# PCB.net
KiCad netlist of a schematic drawn in EasyEDA Pro
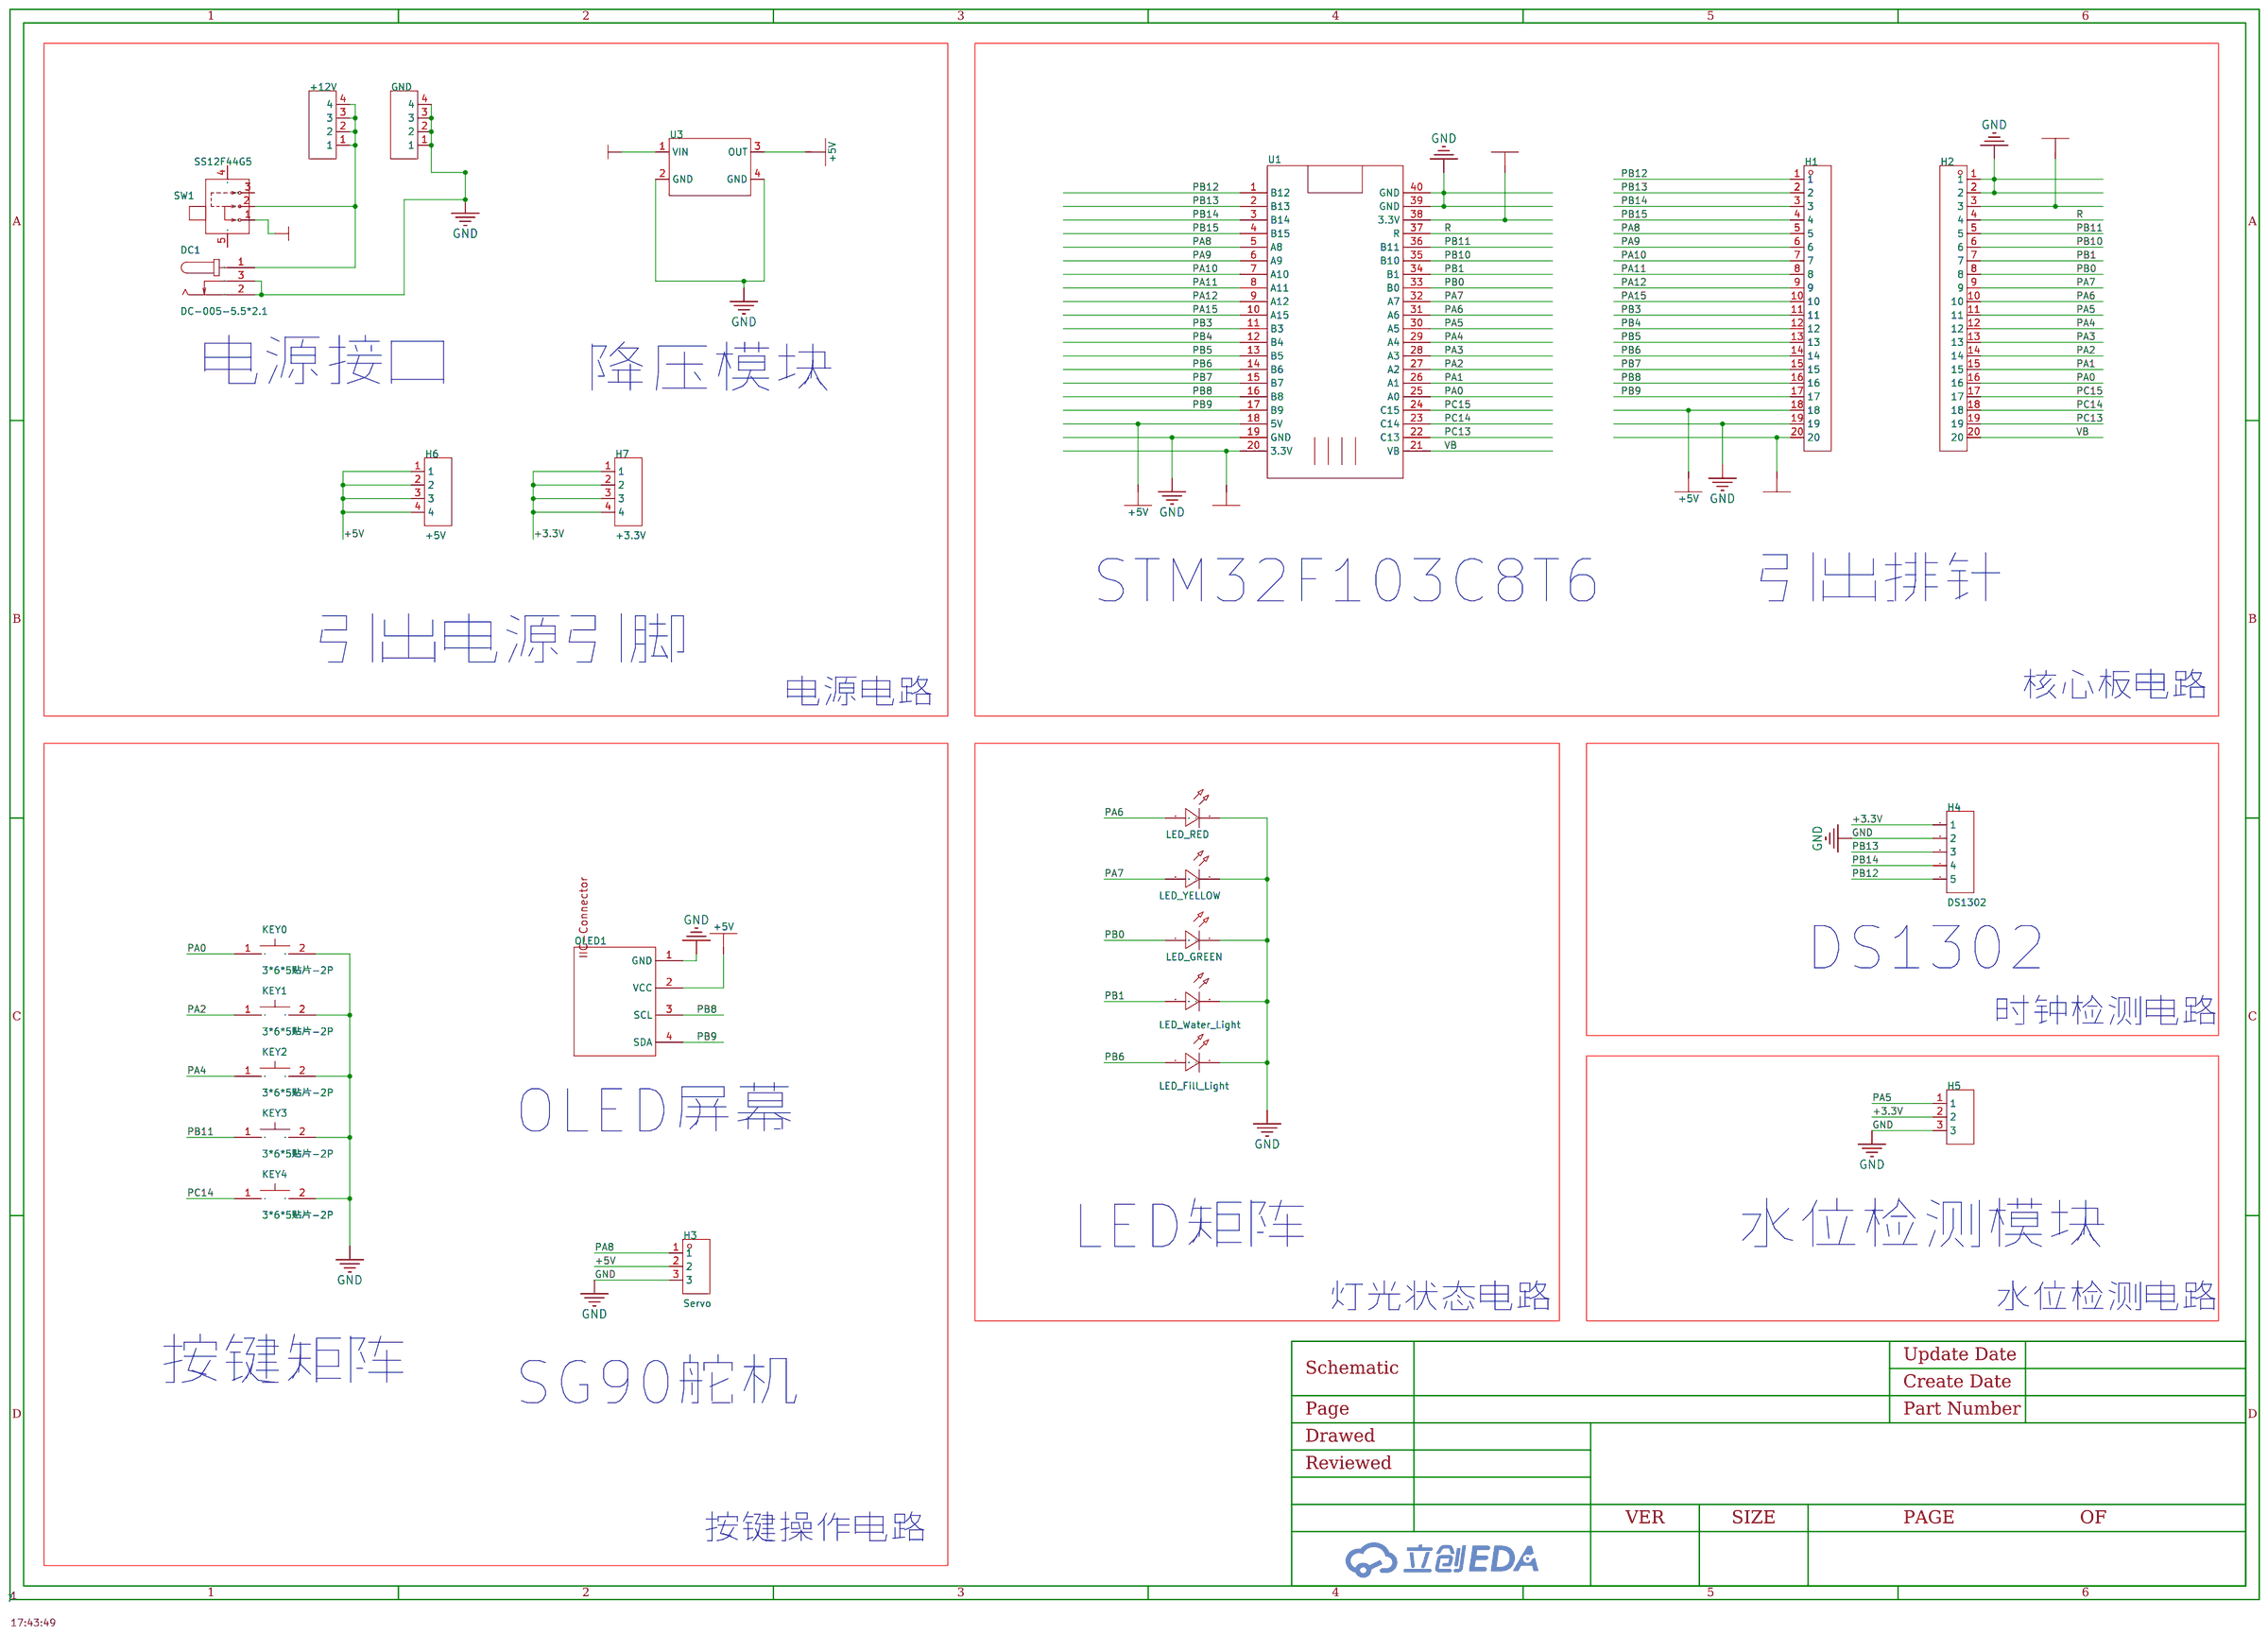
[diagram p0: schematic sheet]

(export (version "E")
  (design (tool "Eeschema 10.0.6"))
  (components
    (comp (ref "+12V")
      (value "~")
      (footprint "easyedapro:HDR-TH_4P-P2.54-V-M")
      (libsource (lib "easyedapro") (part "PZ254V-11-04P"))
    )
    (comp (ref "DC1")
      (value "DC-005-5.5*2.1")
      (footprint "easyedapro:DC-IN-TH_DC-005-2")
      (libsource (lib "easyedapro") (part "DC-005-5.5*2.1"))
    )
    (comp (ref "GND")
      (value "~")
      (footprint "easyedapro:HDR-TH_4P-P2.54-V-M")
      (libsource (lib "easyedapro") (part "PZ254V-11-04P"))
    )
    (comp (ref "H1")
      (value "~")
      (footprint "easyedapro:HDR-TH_20P-P2.54-V-M-1")
      (libsource (lib "easyedapro") (part "HDR_2.54-1x20P"))
    )
    (comp (ref "H2")
      (value "~")
      (footprint "easyedapro:HDR-TH_20P-P2.54-V-M-1")
      (libsource (lib "easyedapro") (part "HDR_2.54-1x20P"))
    )
    (comp (ref "H3")
      (value "Servo")
      (footprint "easyedapro:HDR-TH_3P-P2.54-V-M")
      (libsource (lib "easyedapro") (part "HDR-M_2.54_1x3P"))
    )
    (comp (ref "H4")
      (value "DS1302")
      (footprint "easyedapro:HDR-TH_5P-P2.54-V-F")
      (libsource (lib "easyedapro") (part "Header-Female-2.54_1x5"))
    )
    (comp (ref "H5")
      (value "~")
      (footprint "easyedapro:HDR-TH_3P-P2.54-V-F")
      (libsource (lib "easyedapro") (part "PM254V-11-03-H85"))
    )
    (comp (ref "H6")
      (value "+5V")
      (footprint "easyedapro:HDR-TH_4P-P2.54-V-M")
      (libsource (lib "easyedapro") (part "PZ254V-11-04P"))
    )
    (comp (ref "H7")
      (value "+3.3V")
      (footprint "easyedapro:HDR-TH_4P-P2.54-V-M")
      (libsource (lib "easyedapro") (part "PZ254V-11-04P"))
    )
    (comp (ref "KEY0")
      (value "3*6*5贴片-2P")
      (footprint "easyedapro:SW-SMD_L6.0-W3.5-LS8.0")
      (libsource (lib "easyedapro") (part "3*6*5贴片-2P"))
    )
    (comp (ref "KEY1")
      (value "3*6*5贴片-2P")
      (footprint "easyedapro:SW-SMD_L6.0-W3.5-LS8.0")
      (libsource (lib "easyedapro") (part "3*6*5贴片-2P"))
    )
    (comp (ref "KEY2")
      (value "3*6*5贴片-2P")
      (footprint "easyedapro:SW-SMD_L6.0-W3.5-LS8.0")
      (libsource (lib "easyedapro") (part "3*6*5贴片-2P"))
    )
    (comp (ref "KEY3")
      (value "3*6*5贴片-2P")
      (footprint "easyedapro:SW-SMD_L6.0-W3.5-LS8.0")
      (libsource (lib "easyedapro") (part "3*6*5贴片-2P"))
    )
    (comp (ref "KEY4")
      (value "3*6*5贴片-2P")
      (footprint "easyedapro:SW-SMD_L6.0-W3.5-LS8.0")
      (libsource (lib "easyedapro") (part "3*6*5贴片-2P"))
    )
    (comp (ref "LED_Fill_Light")
      (value "~")
      (footprint "easyedapro:LED_TH-_5mm")
      (libsource (lib "easyedapro") (part "LED_TH-B"))
    )
    (comp (ref "LED_GREEN")
      (value "~")
      (footprint "easyedapro:LED_TH-_5mm")
      (libsource (lib "easyedapro") (part "LED_TH-G"))
    )
    (comp (ref "LED_RED")
      (value "~")
      (footprint "easyedapro:LED_TH-_5mm")
      (libsource (lib "easyedapro") (part "LED_TH-R"))
    )
    (comp (ref "LED_Water_Light")
      (value "~")
      (footprint "easyedapro:LED_TH-_5mm")
      (libsource (lib "easyedapro") (part "LED_TH-B"))
    )
    (comp (ref "LED_YELLOW")
      (value "~")
      (footprint "easyedapro:LED_TH-_5mm")
      (libsource (lib "easyedapro") (part "LED_TH-B"))
    )
    (comp (ref "OLED1")
      (value "~")
      (fields (field (name "Manufacturer Part") "0.96OLED_4P_MODULE_JX"))
      (libsource (lib "easyedapro") (part "0.96OLED_4P_MODULE_JX"))
    )
    (comp (ref "SW1")
      (value "SS12F44G5")
      (footprint "easyedapro:SW-TH_SHOU-HAN_SS12F44G4")
      (description "拨动开关 立式直脚插件 二档 柄高5mm")
      (fields (field (name "Manufacturer") "HanElectricity(瀚源)"))
      (libsource (lib "easyedapro") (part "SS12F44G5"))
    )
    (comp (ref "U1") (value "~") (libsource (lib "easyedapro") (part "STM32F103C8T6核心板")))
    (comp (ref "U3")
      (value "~")
      (footprint "easyedapro:MP1584模块")
      (libsource (lib "easyedapro") (part "MP1584模块"))
    )
  )
  (nets
    (net (code "1") (name "+3.3V") (class "Default")
      (node (ref "H1") (pin "20") (pinfunction "20_20") (pintype "input"))
      (node (ref "H2") (pin "3") (pinfunction "3_3") (pintype "input"))
      (node (ref "H4") (pin "1") (pinfunction "1_1") (pintype "input"))
      (node (ref "H5") (pin "2") (pinfunction "2_2") (pintype "unspecified"))
      (node (ref "H7") (pin "1") (pinfunction "1_1") (pintype "unspecified"))
      (node (ref "H7") (pin "2") (pinfunction "2_2") (pintype "unspecified"))
      (node (ref "H7") (pin "3") (pinfunction "3_3") (pintype "unspecified"))
      (node (ref "H7") (pin "4") (pinfunction "4_4") (pintype "unspecified"))
      (node (ref "U1") (pin "20") (pinfunction "3.3V_20") (pintype "unspecified"))
      (node (ref "U1") (pin "38") (pinfunction "3.3V_38") (pintype "unspecified"))
    )
    (net (code "2") (name "+5V") (class "Default")
      (node (ref "H1") (pin "18") (pinfunction "18_18") (pintype "input"))
      (node (ref "H3") (pin "2") (pinfunction "2_2") (pintype "input"))
      (node (ref "H6") (pin "1") (pinfunction "1_1") (pintype "unspecified"))
      (node (ref "H6") (pin "2") (pinfunction "2_2") (pintype "unspecified"))
      (node (ref "H6") (pin "3") (pinfunction "3_3") (pintype "unspecified"))
      (node (ref "H6") (pin "4") (pinfunction "4_4") (pintype "unspecified"))
      (node (ref "OLED1") (pin "2") (pinfunction "VCC_2") (pintype "input"))
      (node (ref "U1") (pin "18") (pinfunction "5V_18") (pintype "unspecified"))
      (node (ref "U3") (pin "3") (pinfunction "OUT_3") (pintype "unspecified"))
    )
    (net (code "3") (name "+12V") (class "Default")
      (node (ref "SW1") (pin "1") (pinfunction "1_1") (pintype "unspecified"))
      (node (ref "U3") (pin "1") (pinfunction "VIN_1") (pintype "unspecified"))
    )
    (net (code "4") (name "/PA0") (class "Default")
      (node (ref "H2") (pin "16") (pinfunction "16_16") (pintype "input"))
      (node (ref "KEY0") (pin "1") (pinfunction "1_1") (pintype "unspecified"))
      (node (ref "U1") (pin "25") (pinfunction "A0_25") (pintype "unspecified"))
    )
    (net (code "5") (name "/PA1") (class "Default")
      (node (ref "H2") (pin "15") (pinfunction "15_15") (pintype "input"))
      (node (ref "U1") (pin "26") (pinfunction "A1_26") (pintype "unspecified"))
    )
    (net (code "6") (name "/PA2") (class "Default")
      (node (ref "H2") (pin "14") (pinfunction "14_14") (pintype "input"))
      (node (ref "KEY1") (pin "1") (pinfunction "1_1") (pintype "unspecified"))
      (node (ref "U1") (pin "27") (pinfunction "A2_27") (pintype "unspecified"))
    )
    (net (code "7") (name "/PA3") (class "Default")
      (node (ref "H2") (pin "13") (pinfunction "13_13") (pintype "input"))
      (node (ref "U1") (pin "28") (pinfunction "A3_28") (pintype "unspecified"))
    )
    (net (code "8") (name "/PA4") (class "Default")
      (node (ref "H2") (pin "12") (pinfunction "12_12") (pintype "input"))
      (node (ref "KEY2") (pin "1") (pinfunction "1_1") (pintype "unspecified"))
      (node (ref "U1") (pin "29") (pinfunction "A4_29") (pintype "unspecified"))
    )
    (net (code "9") (name "/PA5") (class "Default")
      (node (ref "H2") (pin "11") (pinfunction "11_11") (pintype "input"))
      (node (ref "H5") (pin "1") (pinfunction "1_1") (pintype "unspecified"))
      (node (ref "U1") (pin "30") (pinfunction "A5_30") (pintype "unspecified"))
    )
    (net (code "10") (name "/PA6") (class "Default")
      (node (ref "H2") (pin "10") (pinfunction "10_10") (pintype "input"))
      (node (ref "LED_RED") (pin "1") (pinfunction "C_1") (pintype "input"))
      (node (ref "U1") (pin "31") (pinfunction "A6_31") (pintype "unspecified"))
    )
    (net (code "11") (name "/PA7") (class "Default")
      (node (ref "H2") (pin "9") (pinfunction "9_9") (pintype "input"))
      (node (ref "LED_YELLOW") (pin "1") (pinfunction "C_1") (pintype "input"))
      (node (ref "U1") (pin "32") (pinfunction "A7_32") (pintype "unspecified"))
    )
    (net (code "12") (name "/PA8") (class "Default")
      (node (ref "H1") (pin "5") (pinfunction "5_5") (pintype "input"))
      (node (ref "H3") (pin "1") (pinfunction "1_1") (pintype "input"))
      (node (ref "U1") (pin "5") (pinfunction "A8_5") (pintype "unspecified"))
    )
    (net (code "13") (name "/PA9") (class "Default")
      (node (ref "H1") (pin "6") (pinfunction "6_6") (pintype "input"))
      (node (ref "U1") (pin "6") (pinfunction "A9_6") (pintype "unspecified"))
    )
    (net (code "14") (name "/PA10") (class "Default")
      (node (ref "H1") (pin "7") (pinfunction "7_7") (pintype "input"))
      (node (ref "U1") (pin "7") (pinfunction "A10_7") (pintype "unspecified"))
    )
    (net (code "15") (name "/PA11") (class "Default")
      (node (ref "H1") (pin "8") (pinfunction "8_8") (pintype "input"))
      (node (ref "U1") (pin "8") (pinfunction "A11_8") (pintype "unspecified"))
    )
    (net (code "16") (name "/PA12") (class "Default")
      (node (ref "H1") (pin "9") (pinfunction "9_9") (pintype "input"))
      (node (ref "U1") (pin "9") (pinfunction "A12_9") (pintype "unspecified"))
    )
    (net (code "17") (name "/PA15") (class "Default")
      (node (ref "H1") (pin "10") (pinfunction "10_10") (pintype "input"))
      (node (ref "U1") (pin "10") (pinfunction "A15_10") (pintype "unspecified"))
    )
    (net (code "18") (name "/PB0") (class "Default")
      (node (ref "H2") (pin "8") (pinfunction "8_8") (pintype "input"))
      (node (ref "LED_GREEN") (pin "1") (pinfunction "C_1") (pintype "input"))
      (node (ref "U1") (pin "33") (pinfunction "B0_33") (pintype "unspecified"))
    )
    (net (code "19") (name "/PB1") (class "Default")
      (node (ref "H2") (pin "7") (pinfunction "7_7") (pintype "input"))
      (node (ref "LED_Water_Light") (pin "1") (pinfunction "C_1") (pintype "input"))
      (node (ref "U1") (pin "34") (pinfunction "B1_34") (pintype "unspecified"))
    )
    (net (code "20") (name "/PB3") (class "Default")
      (node (ref "H1") (pin "11") (pinfunction "11_11") (pintype "input"))
      (node (ref "U1") (pin "11") (pinfunction "B3_11") (pintype "unspecified"))
    )
    (net (code "21") (name "/PB4") (class "Default")
      (node (ref "H1") (pin "12") (pinfunction "12_12") (pintype "input"))
      (node (ref "U1") (pin "12") (pinfunction "B4_12") (pintype "unspecified"))
    )
    (net (code "22") (name "/PB5") (class "Default")
      (node (ref "H1") (pin "13") (pinfunction "13_13") (pintype "input"))
      (node (ref "U1") (pin "13") (pinfunction "B5_13") (pintype "unspecified"))
    )
    (net (code "23") (name "/PB6") (class "Default")
      (node (ref "H1") (pin "14") (pinfunction "14_14") (pintype "input"))
      (node (ref "LED_Fill_Light") (pin "1") (pinfunction "C_1") (pintype "input"))
      (node (ref "U1") (pin "14") (pinfunction "B6_14") (pintype "unspecified"))
    )
    (net (code "24") (name "/PB7") (class "Default")
      (node (ref "H1") (pin "15") (pinfunction "15_15") (pintype "input"))
      (node (ref "U1") (pin "15") (pinfunction "B7_15") (pintype "unspecified"))
    )
    (net (code "25") (name "/PB8") (class "Default")
      (node (ref "H1") (pin "16") (pinfunction "16_16") (pintype "input"))
      (node (ref "OLED1") (pin "3") (pinfunction "SCL_3") (pintype "input"))
      (node (ref "U1") (pin "16") (pinfunction "B8_16") (pintype "unspecified"))
    )
    (net (code "26") (name "/PB9") (class "Default")
      (node (ref "H1") (pin "17") (pinfunction "17_17") (pintype "input"))
      (node (ref "OLED1") (pin "4") (pinfunction "SDA_4") (pintype "input"))
      (node (ref "U1") (pin "17") (pinfunction "B9_17") (pintype "unspecified"))
    )
    (net (code "27") (name "/PB10") (class "Default")
      (node (ref "H2") (pin "6") (pinfunction "6_6") (pintype "input"))
      (node (ref "U1") (pin "35") (pinfunction "B10_35") (pintype "unspecified"))
    )
    (net (code "28") (name "/PB11") (class "Default")
      (node (ref "H2") (pin "5") (pinfunction "5_5") (pintype "input"))
      (node (ref "KEY3") (pin "1") (pinfunction "1_1") (pintype "unspecified"))
      (node (ref "U1") (pin "36") (pinfunction "B11_36") (pintype "unspecified"))
    )
    (net (code "29") (name "/PB12") (class "Default")
      (node (ref "H1") (pin "1") (pinfunction "1_1") (pintype "input"))
      (node (ref "H4") (pin "5") (pinfunction "5_5") (pintype "input"))
      (node (ref "U1") (pin "1") (pinfunction "B12_1") (pintype "unspecified"))
    )
    (net (code "30") (name "/PB13") (class "Default")
      (node (ref "H1") (pin "2") (pinfunction "2_2") (pintype "input"))
      (node (ref "H4") (pin "3") (pinfunction "3_3") (pintype "input"))
      (node (ref "U1") (pin "2") (pinfunction "B13_2") (pintype "unspecified"))
    )
    (net (code "31") (name "/PB14") (class "Default")
      (node (ref "H1") (pin "3") (pinfunction "3_3") (pintype "input"))
      (node (ref "H4") (pin "4") (pinfunction "4_4") (pintype "input"))
      (node (ref "U1") (pin "3") (pinfunction "B14_3") (pintype "unspecified"))
    )
    (net (code "32") (name "/PB15") (class "Default")
      (node (ref "H1") (pin "4") (pinfunction "4_4") (pintype "input"))
      (node (ref "U1") (pin "4") (pinfunction "B15_4") (pintype "unspecified"))
    )
    (net (code "33") (name "/PC13") (class "Default")
      (node (ref "H2") (pin "19") (pinfunction "19_19") (pintype "input"))
      (node (ref "U1") (pin "22") (pinfunction "C13_22") (pintype "unspecified"))
    )
    (net (code "34") (name "/PC14") (class "Default")
      (node (ref "H2") (pin "18") (pinfunction "18_18") (pintype "input"))
      (node (ref "KEY4") (pin "1") (pinfunction "1_1") (pintype "unspecified"))
      (node (ref "U1") (pin "23") (pinfunction "C14_23") (pintype "unspecified"))
    )
    (net (code "35") (name "/PC15") (class "Default")
      (node (ref "H2") (pin "17") (pinfunction "17_17") (pintype "input"))
      (node (ref "U1") (pin "24") (pinfunction "C15_24") (pintype "unspecified"))
    )
    (net (code "36") (name "/R") (class "Default")
      (node (ref "H2") (pin "4") (pinfunction "4_4") (pintype "input"))
      (node (ref "U1") (pin "37") (pinfunction "R_37") (pintype "unspecified"))
    )
    (net (code "37") (name "/VB") (class "Default")
      (node (ref "H2") (pin "20") (pinfunction "20_20") (pintype "input"))
      (node (ref "U1") (pin "21") (pinfunction "VB_21") (pintype "unspecified"))
    )
    (net (code "38") (name "GND") (class "Default")
      (node (ref "DC1") (pin "2") (pinfunction "2_2") (pintype "unspecified"))
      (node (ref "DC1") (pin "3") (pinfunction "3_3") (pintype "unspecified"))
      (node (ref "GND") (pin "1") (pinfunction "1_1") (pintype "unspecified"))
      (node (ref "GND") (pin "2") (pinfunction "2_2") (pintype "unspecified"))
      (node (ref "GND") (pin "3") (pinfunction "3_3") (pintype "unspecified"))
      (node (ref "GND") (pin "4") (pinfunction "4_4") (pintype "unspecified"))
      (node (ref "H1") (pin "19") (pinfunction "19_19") (pintype "input"))
      (node (ref "H2") (pin "1") (pinfunction "1_1") (pintype "input"))
      (node (ref "H2") (pin "2") (pinfunction "2_2") (pintype "input"))
      (node (ref "H3") (pin "3") (pinfunction "3_3") (pintype "input"))
      (node (ref "H4") (pin "2") (pinfunction "2_2") (pintype "input"))
      (node (ref "H5") (pin "3") (pinfunction "3_3") (pintype "unspecified"))
      (node (ref "KEY0") (pin "2") (pinfunction "2_2") (pintype "unspecified"))
      (node (ref "KEY1") (pin "2") (pinfunction "2_2") (pintype "unspecified"))
      (node (ref "KEY2") (pin "2") (pinfunction "2_2") (pintype "unspecified"))
      (node (ref "KEY3") (pin "2") (pinfunction "2_2") (pintype "unspecified"))
      (node (ref "KEY4") (pin "2") (pinfunction "2_2") (pintype "unspecified"))
      (node (ref "LED_Fill_Light") (pin "2") (pinfunction "A_2") (pintype "input"))
      (node (ref "LED_GREEN") (pin "2") (pinfunction "A_2") (pintype "input"))
      (node (ref "LED_RED") (pin "2") (pinfunction "A_2") (pintype "input"))
      (node (ref "LED_Water_Light") (pin "2") (pinfunction "A_2") (pintype "input"))
      (node (ref "LED_YELLOW") (pin "2") (pinfunction "A_2") (pintype "input"))
      (node (ref "OLED1") (pin "1") (pinfunction "GND_1") (pintype "input"))
      (node (ref "U1") (pin "19") (pinfunction "GND_19") (pintype "unspecified"))
      (node (ref "U1") (pin "39") (pinfunction "GND_39") (pintype "unspecified"))
      (node (ref "U1") (pin "40") (pinfunction "GND_40") (pintype "unspecified"))
      (node (ref "U3") (pin "2") (pinfunction "GND_2") (pintype "unspecified"))
      (node (ref "U3") (pin "4") (pinfunction "GND_4") (pintype "unspecified"))
    )
    (net (code "39") (name "Net-(+12V-Pad1)") (class "Default")
      (node (ref "+12V") (pin "1") (pinfunction "1_1") (pintype "unspecified"))
      (node (ref "+12V") (pin "2") (pinfunction "2_2") (pintype "unspecified"))
      (node (ref "+12V") (pin "3") (pinfunction "3_3") (pintype "unspecified"))
      (node (ref "+12V") (pin "4") (pinfunction "4_4") (pintype "unspecified"))
      (node (ref "DC1") (pin "1") (pinfunction "1_1") (pintype "unspecified"))
      (node (ref "SW1") (pin "2") (pinfunction "2_2") (pintype "unspecified"))
    )
    (net (code "40") (name "unconnected-(SW1-Pad3)") (class "Default")
      (node (ref "SW1") (pin "3") (pinfunction "3_3") (pintype "unspecified"))
    )
    (net (code "41") (name "unconnected-(SW1-Pad4)") (class "Default")
      (node (ref "SW1") (pin "4") (pinfunction "4_4") (pintype "unspecified"))
    )
    (net (code "42") (name "unconnected-(SW1-Pad5)") (class "Default")
      (node (ref "SW1") (pin "5") (pinfunction "5_5") (pintype "unspecified"))
    )
  )
)
